# LED_Matrix_Driver.net
KiCad netlist of a schematic drawn in Altium Designer
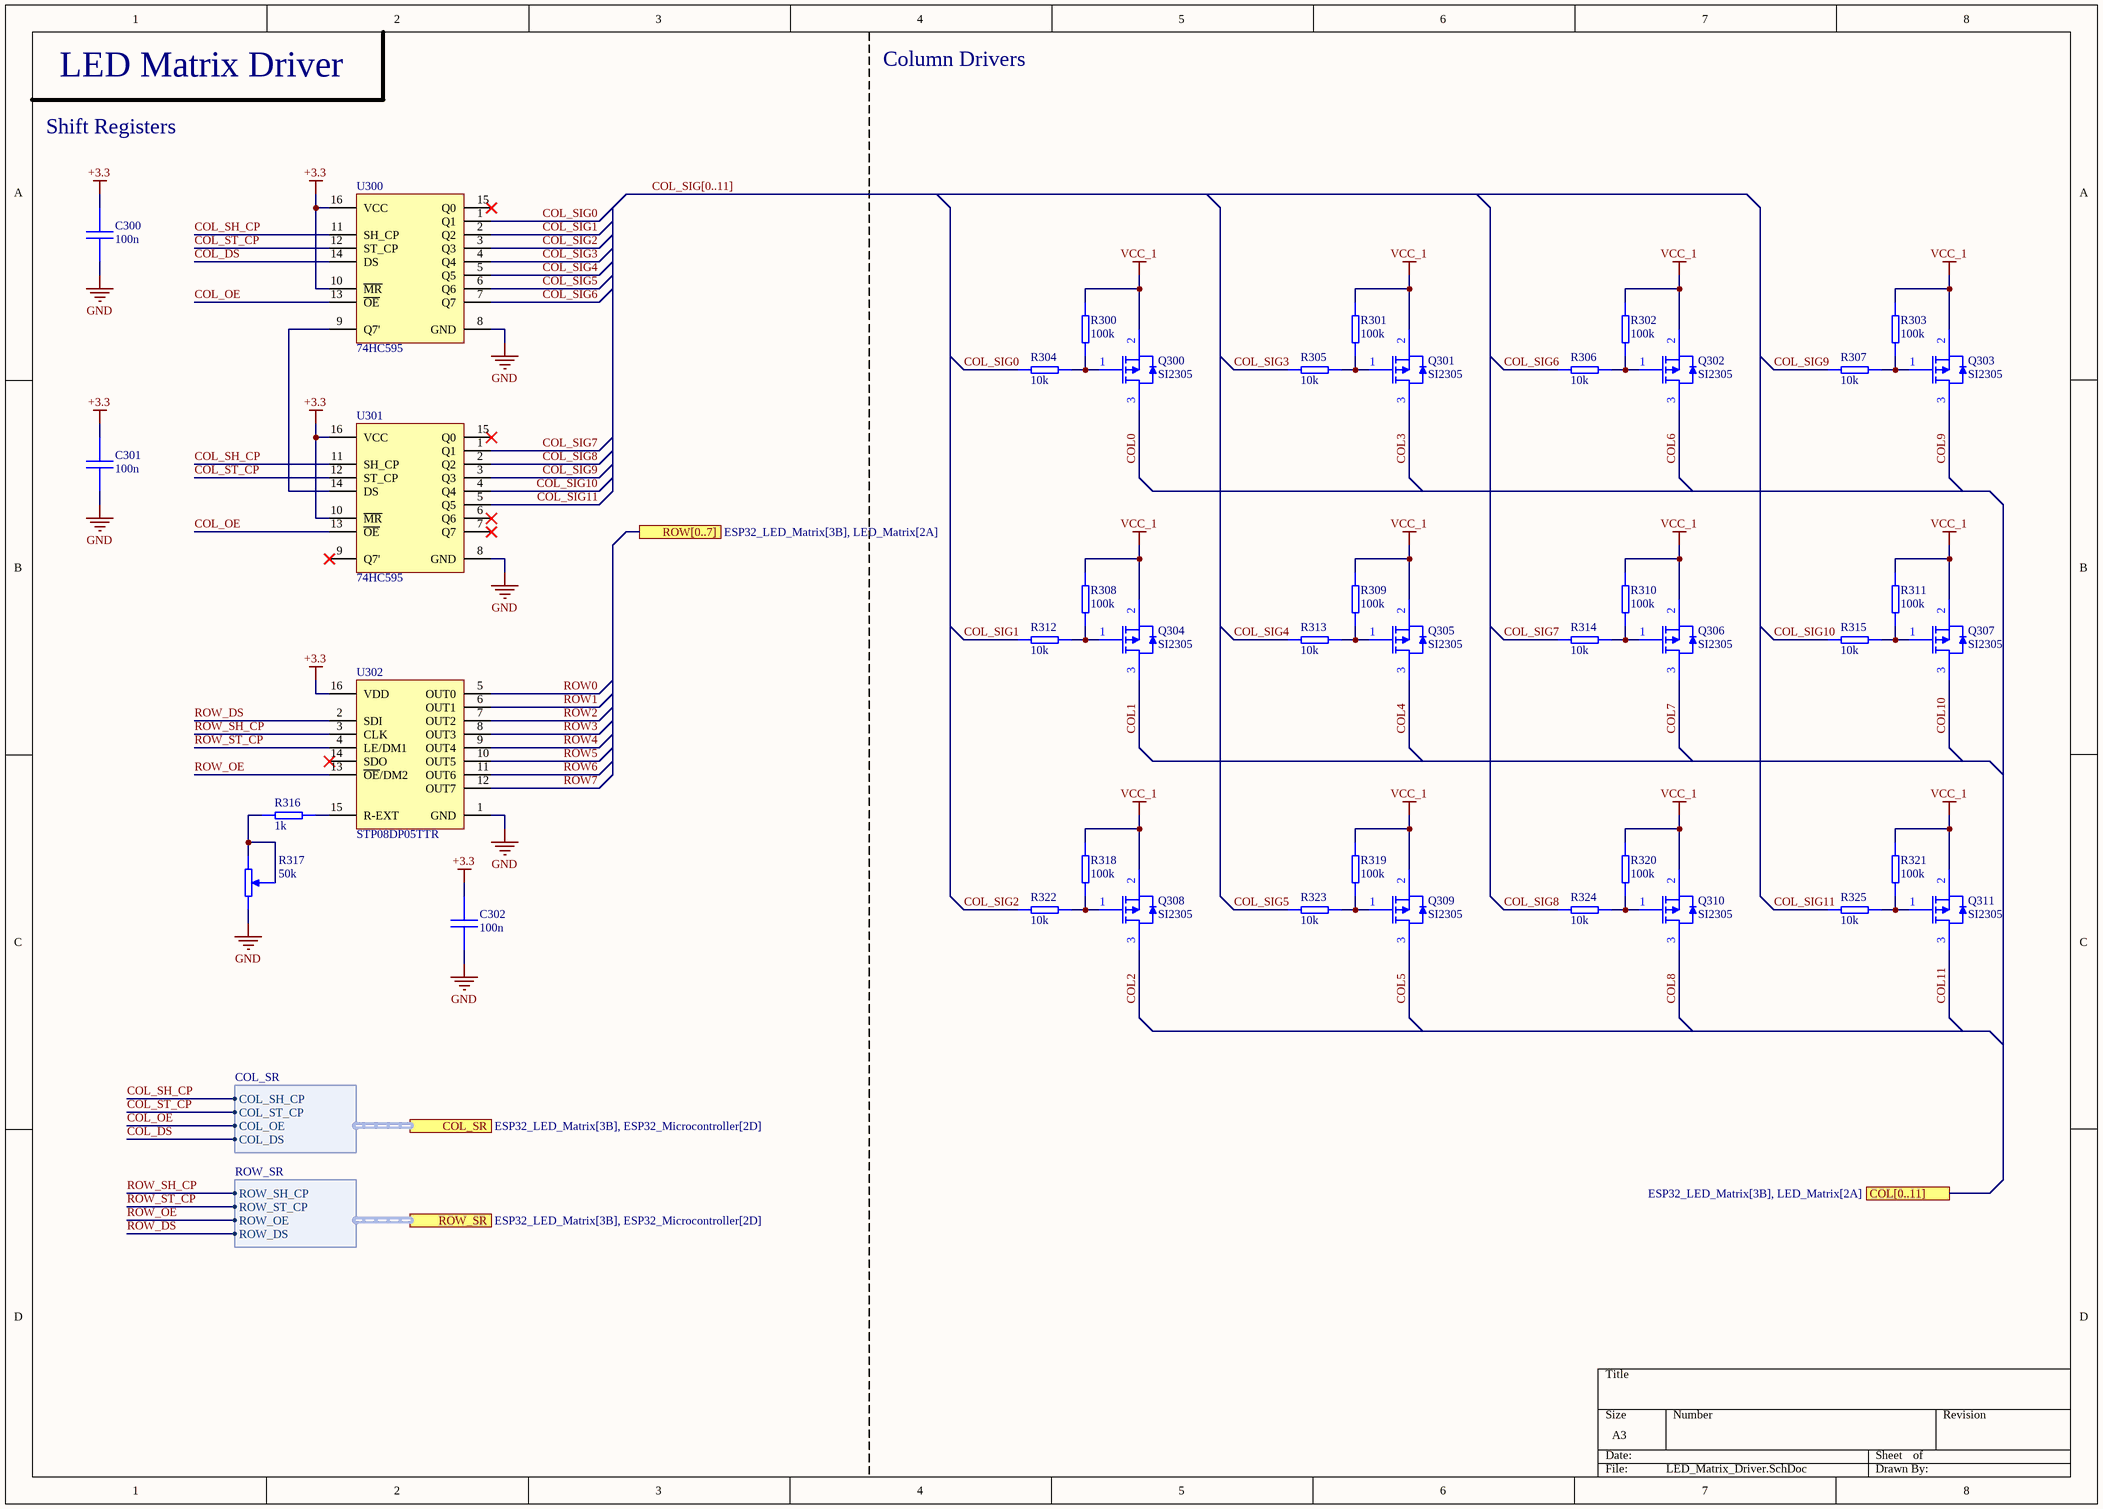
[diagram p0: LED_Matrix_Driver.SchDoc]

(export (version "E")
  (design (tool "Eeschema 10.0.6"))
  (components
    (comp (ref "C300")
      (value "100n")
      (footprint "IEEE_Workshop_Footprints:CAP0805")
      (description "Non Polarized Capacitor")
      (libsource (lib "TD") (part "Capacitor - Non Polarized"))
    )
    (comp (ref "C301")
      (value "100n")
      (footprint "IEEE_Workshop_Footprints:CAP0805")
      (description "Non Polarized Capacitor")
      (libsource (lib "TD") (part "Capacitor - Non Polarized"))
    )
    (comp (ref "C302")
      (value "100n")
      (footprint "IEEE_Workshop_Footprints:CAP0805")
      (description "Non Polarized Capacitor")
      (libsource (lib "TD") (part "Capacitor - Non Polarized"))
    )
    (comp (ref "Q300")
      (value "SI2305")
      (footprint "IEEE_Workshop_Footprints:SOT23")
      (description "General Purpose P-Channel MOSFET")
      (libsource (lib "TD") (part "SI2305"))
    )
    (comp (ref "Q301")
      (value "SI2305")
      (footprint "IEEE_Workshop_Footprints:SOT23")
      (description "General Purpose P-Channel MOSFET")
      (libsource (lib "TD") (part "SI2305"))
    )
    (comp (ref "Q302")
      (value "SI2305")
      (footprint "IEEE_Workshop_Footprints:SOT23")
      (description "General Purpose P-Channel MOSFET")
      (libsource (lib "TD") (part "SI2305"))
    )
    (comp (ref "Q303")
      (value "SI2305")
      (footprint "IEEE_Workshop_Footprints:SOT23")
      (description "General Purpose P-Channel MOSFET")
      (libsource (lib "TD") (part "SI2305"))
    )
    (comp (ref "Q304")
      (value "SI2305")
      (footprint "IEEE_Workshop_Footprints:SOT23")
      (description "General Purpose P-Channel MOSFET")
      (libsource (lib "TD") (part "SI2305"))
    )
    (comp (ref "Q305")
      (value "SI2305")
      (footprint "IEEE_Workshop_Footprints:SOT23")
      (description "General Purpose P-Channel MOSFET")
      (libsource (lib "TD") (part "SI2305"))
    )
    (comp (ref "Q306")
      (value "SI2305")
      (footprint "IEEE_Workshop_Footprints:SOT23")
      (description "General Purpose P-Channel MOSFET")
      (libsource (lib "TD") (part "SI2305"))
    )
    (comp (ref "Q307")
      (value "SI2305")
      (footprint "IEEE_Workshop_Footprints:SOT23")
      (description "General Purpose P-Channel MOSFET")
      (libsource (lib "TD") (part "SI2305"))
    )
    (comp (ref "Q308")
      (value "SI2305")
      (footprint "IEEE_Workshop_Footprints:SOT23")
      (description "General Purpose P-Channel MOSFET")
      (libsource (lib "TD") (part "SI2305"))
    )
    (comp (ref "Q309")
      (value "SI2305")
      (footprint "IEEE_Workshop_Footprints:SOT23")
      (description "General Purpose P-Channel MOSFET")
      (libsource (lib "TD") (part "SI2305"))
    )
    (comp (ref "Q310")
      (value "SI2305")
      (footprint "IEEE_Workshop_Footprints:SOT23")
      (description "General Purpose P-Channel MOSFET")
      (libsource (lib "TD") (part "SI2305"))
    )
    (comp (ref "Q311")
      (value "SI2305")
      (footprint "IEEE_Workshop_Footprints:SOT23")
      (description "General Purpose P-Channel MOSFET")
      (libsource (lib "TD") (part "SI2305"))
    )
    (comp (ref "R300")
      (value "100k")
      (footprint "IEEE_Workshop_Footprints:RESC0805")
      (description "Resistor")
      (libsource (lib "TD") (part "Resistor"))
    )
    (comp (ref "R301")
      (value "100k")
      (footprint "IEEE_Workshop_Footprints:RESC0805")
      (description "Resistor")
      (libsource (lib "TD") (part "Resistor"))
    )
    (comp (ref "R302")
      (value "100k")
      (footprint "IEEE_Workshop_Footprints:RESC0805")
      (description "Resistor")
      (libsource (lib "TD") (part "Resistor"))
    )
    (comp (ref "R303")
      (value "100k")
      (footprint "IEEE_Workshop_Footprints:RESC0805")
      (description "Resistor")
      (libsource (lib "TD") (part "Resistor"))
    )
    (comp (ref "R304")
      (value "10k")
      (footprint "IEEE_Workshop_Footprints:RESC0805")
      (description "Resistor")
      (libsource (lib "TD") (part "Resistor"))
    )
    (comp (ref "R305")
      (value "10k")
      (footprint "IEEE_Workshop_Footprints:RESC0805")
      (description "Resistor")
      (libsource (lib "TD") (part "Resistor"))
    )
    (comp (ref "R306")
      (value "10k")
      (footprint "IEEE_Workshop_Footprints:RESC0805")
      (description "Resistor")
      (libsource (lib "TD") (part "Resistor"))
    )
    (comp (ref "R307")
      (value "10k")
      (footprint "IEEE_Workshop_Footprints:RESC0805")
      (description "Resistor")
      (libsource (lib "TD") (part "Resistor"))
    )
    (comp (ref "R308")
      (value "100k")
      (footprint "IEEE_Workshop_Footprints:RESC0805")
      (description "Resistor")
      (libsource (lib "TD") (part "Resistor"))
    )
    (comp (ref "R309")
      (value "100k")
      (footprint "IEEE_Workshop_Footprints:RESC0805")
      (description "Resistor")
      (libsource (lib "TD") (part "Resistor"))
    )
    (comp (ref "R310")
      (value "100k")
      (footprint "IEEE_Workshop_Footprints:RESC0805")
      (description "Resistor")
      (libsource (lib "TD") (part "Resistor"))
    )
    (comp (ref "R311")
      (value "100k")
      (footprint "IEEE_Workshop_Footprints:RESC0805")
      (description "Resistor")
      (libsource (lib "TD") (part "Resistor"))
    )
    (comp (ref "R312")
      (value "10k")
      (footprint "IEEE_Workshop_Footprints:RESC0805")
      (description "Resistor")
      (libsource (lib "TD") (part "Resistor"))
    )
    (comp (ref "R313")
      (value "10k")
      (footprint "IEEE_Workshop_Footprints:RESC0805")
      (description "Resistor")
      (libsource (lib "TD") (part "Resistor"))
    )
    (comp (ref "R314")
      (value "10k")
      (footprint "IEEE_Workshop_Footprints:RESC0805")
      (description "Resistor")
      (libsource (lib "TD") (part "Resistor"))
    )
    (comp (ref "R315")
      (value "10k")
      (footprint "IEEE_Workshop_Footprints:RESC0805")
      (description "Resistor")
      (libsource (lib "TD") (part "Resistor"))
    )
    (comp (ref "R316")
      (value "1k")
      (footprint "IEEE_Workshop_Footprints:RESC0805")
      (description "Resistor")
      (libsource (lib "TD") (part "Resistor"))
    )
    (comp (ref "R317")
      (value "50k")
      (footprint "IEEE_Workshop_Footprints:3339P1103LF")
      (description "Potentionmeter")
      (libsource (lib "TD") (part "Potentiometer"))
    )
    (comp (ref "R318")
      (value "100k")
      (footprint "IEEE_Workshop_Footprints:RESC0805")
      (description "Resistor")
      (libsource (lib "TD") (part "Resistor"))
    )
    (comp (ref "R319")
      (value "100k")
      (footprint "IEEE_Workshop_Footprints:RESC0805")
      (description "Resistor")
      (libsource (lib "TD") (part "Resistor"))
    )
    (comp (ref "R320")
      (value "100k")
      (footprint "IEEE_Workshop_Footprints:RESC0805")
      (description "Resistor")
      (libsource (lib "TD") (part "Resistor"))
    )
    (comp (ref "R321")
      (value "100k")
      (footprint "IEEE_Workshop_Footprints:RESC0805")
      (description "Resistor")
      (libsource (lib "TD") (part "Resistor"))
    )
    (comp (ref "R322")
      (value "10k")
      (footprint "IEEE_Workshop_Footprints:RESC0805")
      (description "Resistor")
      (libsource (lib "TD") (part "Resistor"))
    )
    (comp (ref "R323")
      (value "10k")
      (footprint "IEEE_Workshop_Footprints:RESC0805")
      (description "Resistor")
      (libsource (lib "TD") (part "Resistor"))
    )
    (comp (ref "R324")
      (value "10k")
      (footprint "IEEE_Workshop_Footprints:RESC0805")
      (description "Resistor")
      (libsource (lib "TD") (part "Resistor"))
    )
    (comp (ref "R325")
      (value "10k")
      (footprint "IEEE_Workshop_Footprints:RESC0805")
      (description "Resistor")
      (libsource (lib "TD") (part "Resistor"))
    )
    (comp (ref "U300")
      (value "74HC595")
      (footprint "IEEE_Workshop_Footprints:TSSOP16")
      (description "Shift Register")
      (libsource (lib "TD") (part "74HC595"))
    )
    (comp (ref "U301")
      (value "74HC595")
      (footprint "IEEE_Workshop_Footprints:TSSOP16")
      (description "Shift Register")
      (libsource (lib "TD") (part "74HC595"))
    )
    (comp (ref "U302")
      (value "STP08DP05TTR")
      (footprint "IEEE_Workshop_Footprints:TSSOP16")
      (description "LED Driver")
      (fields (field (name "MOUSER PART NUMBER") "511-STP08DP05TTR"))
      (libsource (lib "TD") (part "STP08DP05TTR"))
    )
  )
  (nets
    (net (code "3") (name "+3.3") (class "Default")
      (node (ref "C300") (pin "1") (pintype "passive"))
      (node (ref "C301") (pin "1") (pintype "passive"))
      (node (ref "C302") (pin "1") (pintype "passive"))
      (node (ref "U300") (pin "10") (pinfunction "~{MR}_10") (pintype "passive"))
      (node (ref "U300") (pin "16") (pinfunction "VCC_16") (pintype "passive"))
      (node (ref "U301") (pin "10") (pinfunction "~{MR}_10") (pintype "passive"))
      (node (ref "U301") (pin "16") (pinfunction "VCC_16") (pintype "passive"))
      (node (ref "U302") (pin "16") (pinfunction "VDD_16") (pintype "passive"))
    )
    (net (code "4") (name "/COL0") (class "Default")
      (node (ref "Q300") (pin "3") (pinfunction "D_3") (pintype "passive"))
    )
    (net (code "5") (name "/COL1") (class "Default")
      (node (ref "Q304") (pin "3") (pinfunction "D_3") (pintype "passive"))
    )
    (net (code "6") (name "/COL2") (class "Default")
      (node (ref "Q308") (pin "3") (pinfunction "D_3") (pintype "passive"))
    )
    (net (code "7") (name "/COL3") (class "Default")
      (node (ref "Q301") (pin "3") (pinfunction "D_3") (pintype "passive"))
    )
    (net (code "8") (name "/COL4") (class "Default")
      (node (ref "Q305") (pin "3") (pinfunction "D_3") (pintype "passive"))
    )
    (net (code "9") (name "/COL5") (class "Default")
      (node (ref "Q309") (pin "3") (pinfunction "D_3") (pintype "passive"))
    )
    (net (code "10") (name "/COL6") (class "Default")
      (node (ref "Q302") (pin "3") (pinfunction "D_3") (pintype "passive"))
    )
    (net (code "11") (name "/COL7") (class "Default")
      (node (ref "Q306") (pin "3") (pinfunction "D_3") (pintype "passive"))
    )
    (net (code "12") (name "/COL8") (class "Default")
      (node (ref "Q310") (pin "3") (pinfunction "D_3") (pintype "passive"))
    )
    (net (code "13") (name "/COL9") (class "Default")
      (node (ref "Q303") (pin "3") (pinfunction "D_3") (pintype "passive"))
    )
    (net (code "14") (name "/COL10") (class "Default")
      (node (ref "Q307") (pin "3") (pinfunction "D_3") (pintype "passive"))
    )
    (net (code "15") (name "/COL11") (class "Default")
      (node (ref "Q311") (pin "3") (pinfunction "D_3") (pintype "passive"))
    )
    (net (code "17") (name "/COL_DS") (class "Default")
      (node (ref "U300") (pin "14") (pinfunction "DS_14") (pintype "passive"))
    )
    (net (code "18") (name "/COL_OE") (class "Default")
      (node (ref "U300") (pin "13") (pinfunction "~{OE}_13") (pintype "passive"))
      (node (ref "U301") (pin "13") (pinfunction "~{OE}_13") (pintype "passive"))
    )
    (net (code "19") (name "/COL_SH_CP") (class "Default")
      (node (ref "U300") (pin "11") (pinfunction "SH_CP_11") (pintype "passive"))
      (node (ref "U301") (pin "11") (pinfunction "SH_CP_11") (pintype "passive"))
    )
    (net (code "20") (name "/COL_SIG0") (class "Default")
      (node (ref "R304") (pin "1") (pintype "passive"))
      (node (ref "U300") (pin "1") (pinfunction "Q1_1") (pintype "passive"))
    )
    (net (code "21") (name "/COL_SIG1") (class "Default")
      (node (ref "R312") (pin "1") (pintype "passive"))
      (node (ref "U300") (pin "2") (pinfunction "Q2_2") (pintype "passive"))
    )
    (net (code "22") (name "/COL_SIG2") (class "Default")
      (node (ref "R322") (pin "1") (pintype "passive"))
      (node (ref "U300") (pin "3") (pinfunction "Q3_3") (pintype "passive"))
    )
    (net (code "23") (name "/COL_SIG3") (class "Default")
      (node (ref "R305") (pin "1") (pintype "passive"))
      (node (ref "U300") (pin "4") (pinfunction "Q4_4") (pintype "passive"))
    )
    (net (code "24") (name "/COL_SIG4") (class "Default")
      (node (ref "R313") (pin "1") (pintype "passive"))
      (node (ref "U300") (pin "5") (pinfunction "Q5_5") (pintype "passive"))
    )
    (net (code "25") (name "/COL_SIG5") (class "Default")
      (node (ref "R323") (pin "1") (pintype "passive"))
      (node (ref "U300") (pin "6") (pinfunction "Q6_6") (pintype "passive"))
    )
    (net (code "26") (name "/COL_SIG6") (class "Default")
      (node (ref "R306") (pin "1") (pintype "passive"))
      (node (ref "U300") (pin "7") (pinfunction "Q7_7") (pintype "passive"))
    )
    (net (code "27") (name "/COL_SIG7") (class "Default")
      (node (ref "R314") (pin "1") (pintype "passive"))
      (node (ref "U301") (pin "1") (pinfunction "Q1_1") (pintype "passive"))
    )
    (net (code "28") (name "/COL_SIG8") (class "Default")
      (node (ref "R324") (pin "1") (pintype "passive"))
      (node (ref "U301") (pin "2") (pinfunction "Q2_2") (pintype "passive"))
    )
    (net (code "29") (name "/COL_SIG9") (class "Default")
      (node (ref "R307") (pin "1") (pintype "passive"))
      (node (ref "U301") (pin "3") (pinfunction "Q3_3") (pintype "passive"))
    )
    (net (code "30") (name "/COL_SIG10") (class "Default")
      (node (ref "R315") (pin "1") (pintype "passive"))
      (node (ref "U301") (pin "4") (pinfunction "Q4_4") (pintype "passive"))
    )
    (net (code "31") (name "/COL_SIG11") (class "Default")
      (node (ref "R325") (pin "1") (pintype "passive"))
      (node (ref "U301") (pin "5") (pinfunction "Q5_5") (pintype "passive"))
    )
    (net (code "33") (name "/COL_ST_CP") (class "Default")
      (node (ref "U300") (pin "12") (pinfunction "ST_CP_12") (pintype "passive"))
      (node (ref "U301") (pin "12") (pinfunction "ST_CP_12") (pintype "passive"))
    )
    (net (code "34") (name "/ROW0") (class "Default")
      (node (ref "U302") (pin "5") (pinfunction "OUT0_5") (pintype "passive"))
    )
    (net (code "35") (name "/ROW1") (class "Default")
      (node (ref "U302") (pin "6") (pinfunction "OUT1_6") (pintype "passive"))
    )
    (net (code "36") (name "/ROW2") (class "Default")
      (node (ref "U302") (pin "7") (pinfunction "OUT2_7") (pintype "passive"))
    )
    (net (code "37") (name "/ROW3") (class "Default")
      (node (ref "U302") (pin "8") (pinfunction "OUT3_8") (pintype "passive"))
    )
    (net (code "38") (name "/ROW4") (class "Default")
      (node (ref "U302") (pin "9") (pinfunction "OUT4_9") (pintype "passive"))
    )
    (net (code "39") (name "/ROW5") (class "Default")
      (node (ref "U302") (pin "10") (pinfunction "OUT5_10") (pintype "passive"))
    )
    (net (code "40") (name "/ROW6") (class "Default")
      (node (ref "U302") (pin "11") (pinfunction "OUT6_11") (pintype "passive"))
    )
    (net (code "41") (name "/ROW7") (class "Default")
      (node (ref "U302") (pin "12") (pinfunction "OUT7_12") (pintype "passive"))
    )
    (net (code "43") (name "/ROW_DS") (class "Default")
      (node (ref "U302") (pin "2") (pinfunction "SDI_2") (pintype "passive"))
    )
    (net (code "44") (name "/ROW_OE") (class "Default")
      (node (ref "U302") (pin "13") (pinfunction "~{OE}/DM2_13") (pintype "passive"))
    )
    (net (code "45") (name "/ROW_SH_CP") (class "Default")
      (node (ref "U302") (pin "3") (pinfunction "CLK_3") (pintype "passive"))
    )
    (net (code "46") (name "/ROW_ST_CP") (class "Default")
      (node (ref "U302") (pin "4") (pinfunction "LE/DM1_4") (pintype "passive"))
    )
    (net (code "49") (name "GND") (class "Default")
      (node (ref "C300") (pin "2") (pintype "passive"))
      (node (ref "C301") (pin "2") (pintype "passive"))
      (node (ref "C302") (pin "2") (pintype "passive"))
      (node (ref "R317") (pin "3") (pintype "passive"))
      (node (ref "U300") (pin "8") (pinfunction "GND_8") (pintype "passive"))
      (node (ref "U301") (pin "8") (pinfunction "GND_8") (pintype "passive"))
      (node (ref "U302") (pin "1") (pinfunction "GND_1") (pintype "passive"))
    )
    (net (code "50") (name "Net-(Q300-G)") (class "Default")
      (node (ref "Q300") (pin "1") (pinfunction "G_1") (pintype "passive"))
      (node (ref "R300") (pin "2") (pintype "passive"))
      (node (ref "R304") (pin "2") (pintype "passive"))
    )
    (net (code "51") (name "Net-(Q301-G)") (class "Default")
      (node (ref "Q301") (pin "1") (pinfunction "G_1") (pintype "passive"))
      (node (ref "R301") (pin "2") (pintype "passive"))
      (node (ref "R305") (pin "2") (pintype "passive"))
    )
    (net (code "52") (name "Net-(Q302-G)") (class "Default")
      (node (ref "Q302") (pin "1") (pinfunction "G_1") (pintype "passive"))
      (node (ref "R302") (pin "2") (pintype "passive"))
      (node (ref "R306") (pin "2") (pintype "passive"))
    )
    (net (code "53") (name "Net-(Q303-G)") (class "Default")
      (node (ref "Q303") (pin "1") (pinfunction "G_1") (pintype "passive"))
      (node (ref "R303") (pin "2") (pintype "passive"))
      (node (ref "R307") (pin "2") (pintype "passive"))
    )
    (net (code "54") (name "Net-(Q304-G)") (class "Default")
      (node (ref "Q304") (pin "1") (pinfunction "G_1") (pintype "passive"))
      (node (ref "R308") (pin "2") (pintype "passive"))
      (node (ref "R312") (pin "2") (pintype "passive"))
    )
    (net (code "55") (name "Net-(Q305-G)") (class "Default")
      (node (ref "Q305") (pin "1") (pinfunction "G_1") (pintype "passive"))
      (node (ref "R309") (pin "2") (pintype "passive"))
      (node (ref "R313") (pin "2") (pintype "passive"))
    )
    (net (code "56") (name "Net-(Q306-G)") (class "Default")
      (node (ref "Q306") (pin "1") (pinfunction "G_1") (pintype "passive"))
      (node (ref "R310") (pin "2") (pintype "passive"))
      (node (ref "R314") (pin "2") (pintype "passive"))
    )
    (net (code "57") (name "Net-(Q307-G)") (class "Default")
      (node (ref "Q307") (pin "1") (pinfunction "G_1") (pintype "passive"))
      (node (ref "R311") (pin "2") (pintype "passive"))
      (node (ref "R315") (pin "2") (pintype "passive"))
    )
    (net (code "58") (name "Net-(Q308-G)") (class "Default")
      (node (ref "Q308") (pin "1") (pinfunction "G_1") (pintype "passive"))
      (node (ref "R318") (pin "2") (pintype "passive"))
      (node (ref "R322") (pin "2") (pintype "passive"))
    )
    (net (code "59") (name "Net-(Q309-G)") (class "Default")
      (node (ref "Q309") (pin "1") (pinfunction "G_1") (pintype "passive"))
      (node (ref "R319") (pin "2") (pintype "passive"))
      (node (ref "R323") (pin "2") (pintype "passive"))
    )
    (net (code "60") (name "Net-(Q310-G)") (class "Default")
      (node (ref "Q310") (pin "1") (pinfunction "G_1") (pintype "passive"))
      (node (ref "R320") (pin "2") (pintype "passive"))
      (node (ref "R324") (pin "2") (pintype "passive"))
    )
    (net (code "61") (name "Net-(Q311-G)") (class "Default")
      (node (ref "Q311") (pin "1") (pinfunction "G_1") (pintype "passive"))
      (node (ref "R321") (pin "2") (pintype "passive"))
      (node (ref "R325") (pin "2") (pintype "passive"))
    )
    (net (code "62") (name "Net-(R316-Pad2)") (class "Default")
      (node (ref "R316") (pin "2") (pintype "passive"))
      (node (ref "R317") (pin "1") (pintype "passive"))
      (node (ref "R317") (pin "2") (pintype "passive"))
    )
    (net (code "63") (name "Net-(U300-Q7')") (class "Default")
      (node (ref "U300") (pin "9") (pinfunction "Q7'_9") (pintype "passive"))
      (node (ref "U301") (pin "14") (pinfunction "DS_14") (pintype "passive"))
    )
    (net (code "64") (name "Net-(U302-R-EXT)") (class "Default")
      (node (ref "R316") (pin "1") (pintype "passive"))
      (node (ref "U302") (pin "15") (pinfunction "R-EXT_15") (pintype "passive"))
    )
    (net (code "65") (name "VCC_1") (class "Default")
      (node (ref "Q300") (pin "2") (pinfunction "S_2") (pintype "passive"))
      (node (ref "Q301") (pin "2") (pinfunction "S_2") (pintype "passive"))
      (node (ref "Q302") (pin "2") (pinfunction "S_2") (pintype "passive"))
      (node (ref "Q303") (pin "2") (pinfunction "S_2") (pintype "passive"))
      (node (ref "Q304") (pin "2") (pinfunction "S_2") (pintype "passive"))
      (node (ref "Q305") (pin "2") (pinfunction "S_2") (pintype "passive"))
      (node (ref "Q306") (pin "2") (pinfunction "S_2") (pintype "passive"))
      (node (ref "Q307") (pin "2") (pinfunction "S_2") (pintype "passive"))
      (node (ref "Q308") (pin "2") (pinfunction "S_2") (pintype "passive"))
      (node (ref "Q309") (pin "2") (pinfunction "S_2") (pintype "passive"))
      (node (ref "Q310") (pin "2") (pinfunction "S_2") (pintype "passive"))
      (node (ref "Q311") (pin "2") (pinfunction "S_2") (pintype "passive"))
      (node (ref "R300") (pin "1") (pintype "passive"))
      (node (ref "R301") (pin "1") (pintype "passive"))
      (node (ref "R302") (pin "1") (pintype "passive"))
      (node (ref "R303") (pin "1") (pintype "passive"))
      (node (ref "R308") (pin "1") (pintype "passive"))
      (node (ref "R309") (pin "1") (pintype "passive"))
      (node (ref "R310") (pin "1") (pintype "passive"))
      (node (ref "R311") (pin "1") (pintype "passive"))
      (node (ref "R318") (pin "1") (pintype "passive"))
      (node (ref "R319") (pin "1") (pintype "passive"))
      (node (ref "R320") (pin "1") (pintype "passive"))
      (node (ref "R321") (pin "1") (pintype "passive"))
    )
    (net (code "66") (name "unconnected-(U300-Q0-Pad15)") (class "Default")
      (node (ref "U300") (pin "15") (pinfunction "Q0_15") (pintype "passive+no_connect"))
    )
    (net (code "67") (name "unconnected-(U301-Q0-Pad15)") (class "Default")
      (node (ref "U301") (pin "15") (pinfunction "Q0_15") (pintype "passive+no_connect"))
    )
    (net (code "68") (name "unconnected-(U301-Q6-Pad6)") (class "Default")
      (node (ref "U301") (pin "6") (pinfunction "Q6_6") (pintype "passive+no_connect"))
    )
    (net (code "69") (name "unconnected-(U301-Q7'-Pad9)") (class "Default")
      (node (ref "U301") (pin "9") (pinfunction "Q7'_9") (pintype "passive+no_connect"))
    )
    (net (code "70") (name "unconnected-(U301-Q7-Pad7)") (class "Default")
      (node (ref "U301") (pin "7") (pinfunction "Q7_7") (pintype "passive+no_connect"))
    )
    (net (code "71") (name "unconnected-(U302-SDO-Pad14)") (class "Default")
      (node (ref "U302") (pin "14") (pinfunction "SDO_14") (pintype "passive+no_connect"))
    )
  )
)
